# 8085_try2.net
KiCad netlist of a schematic drawn in EAGLE
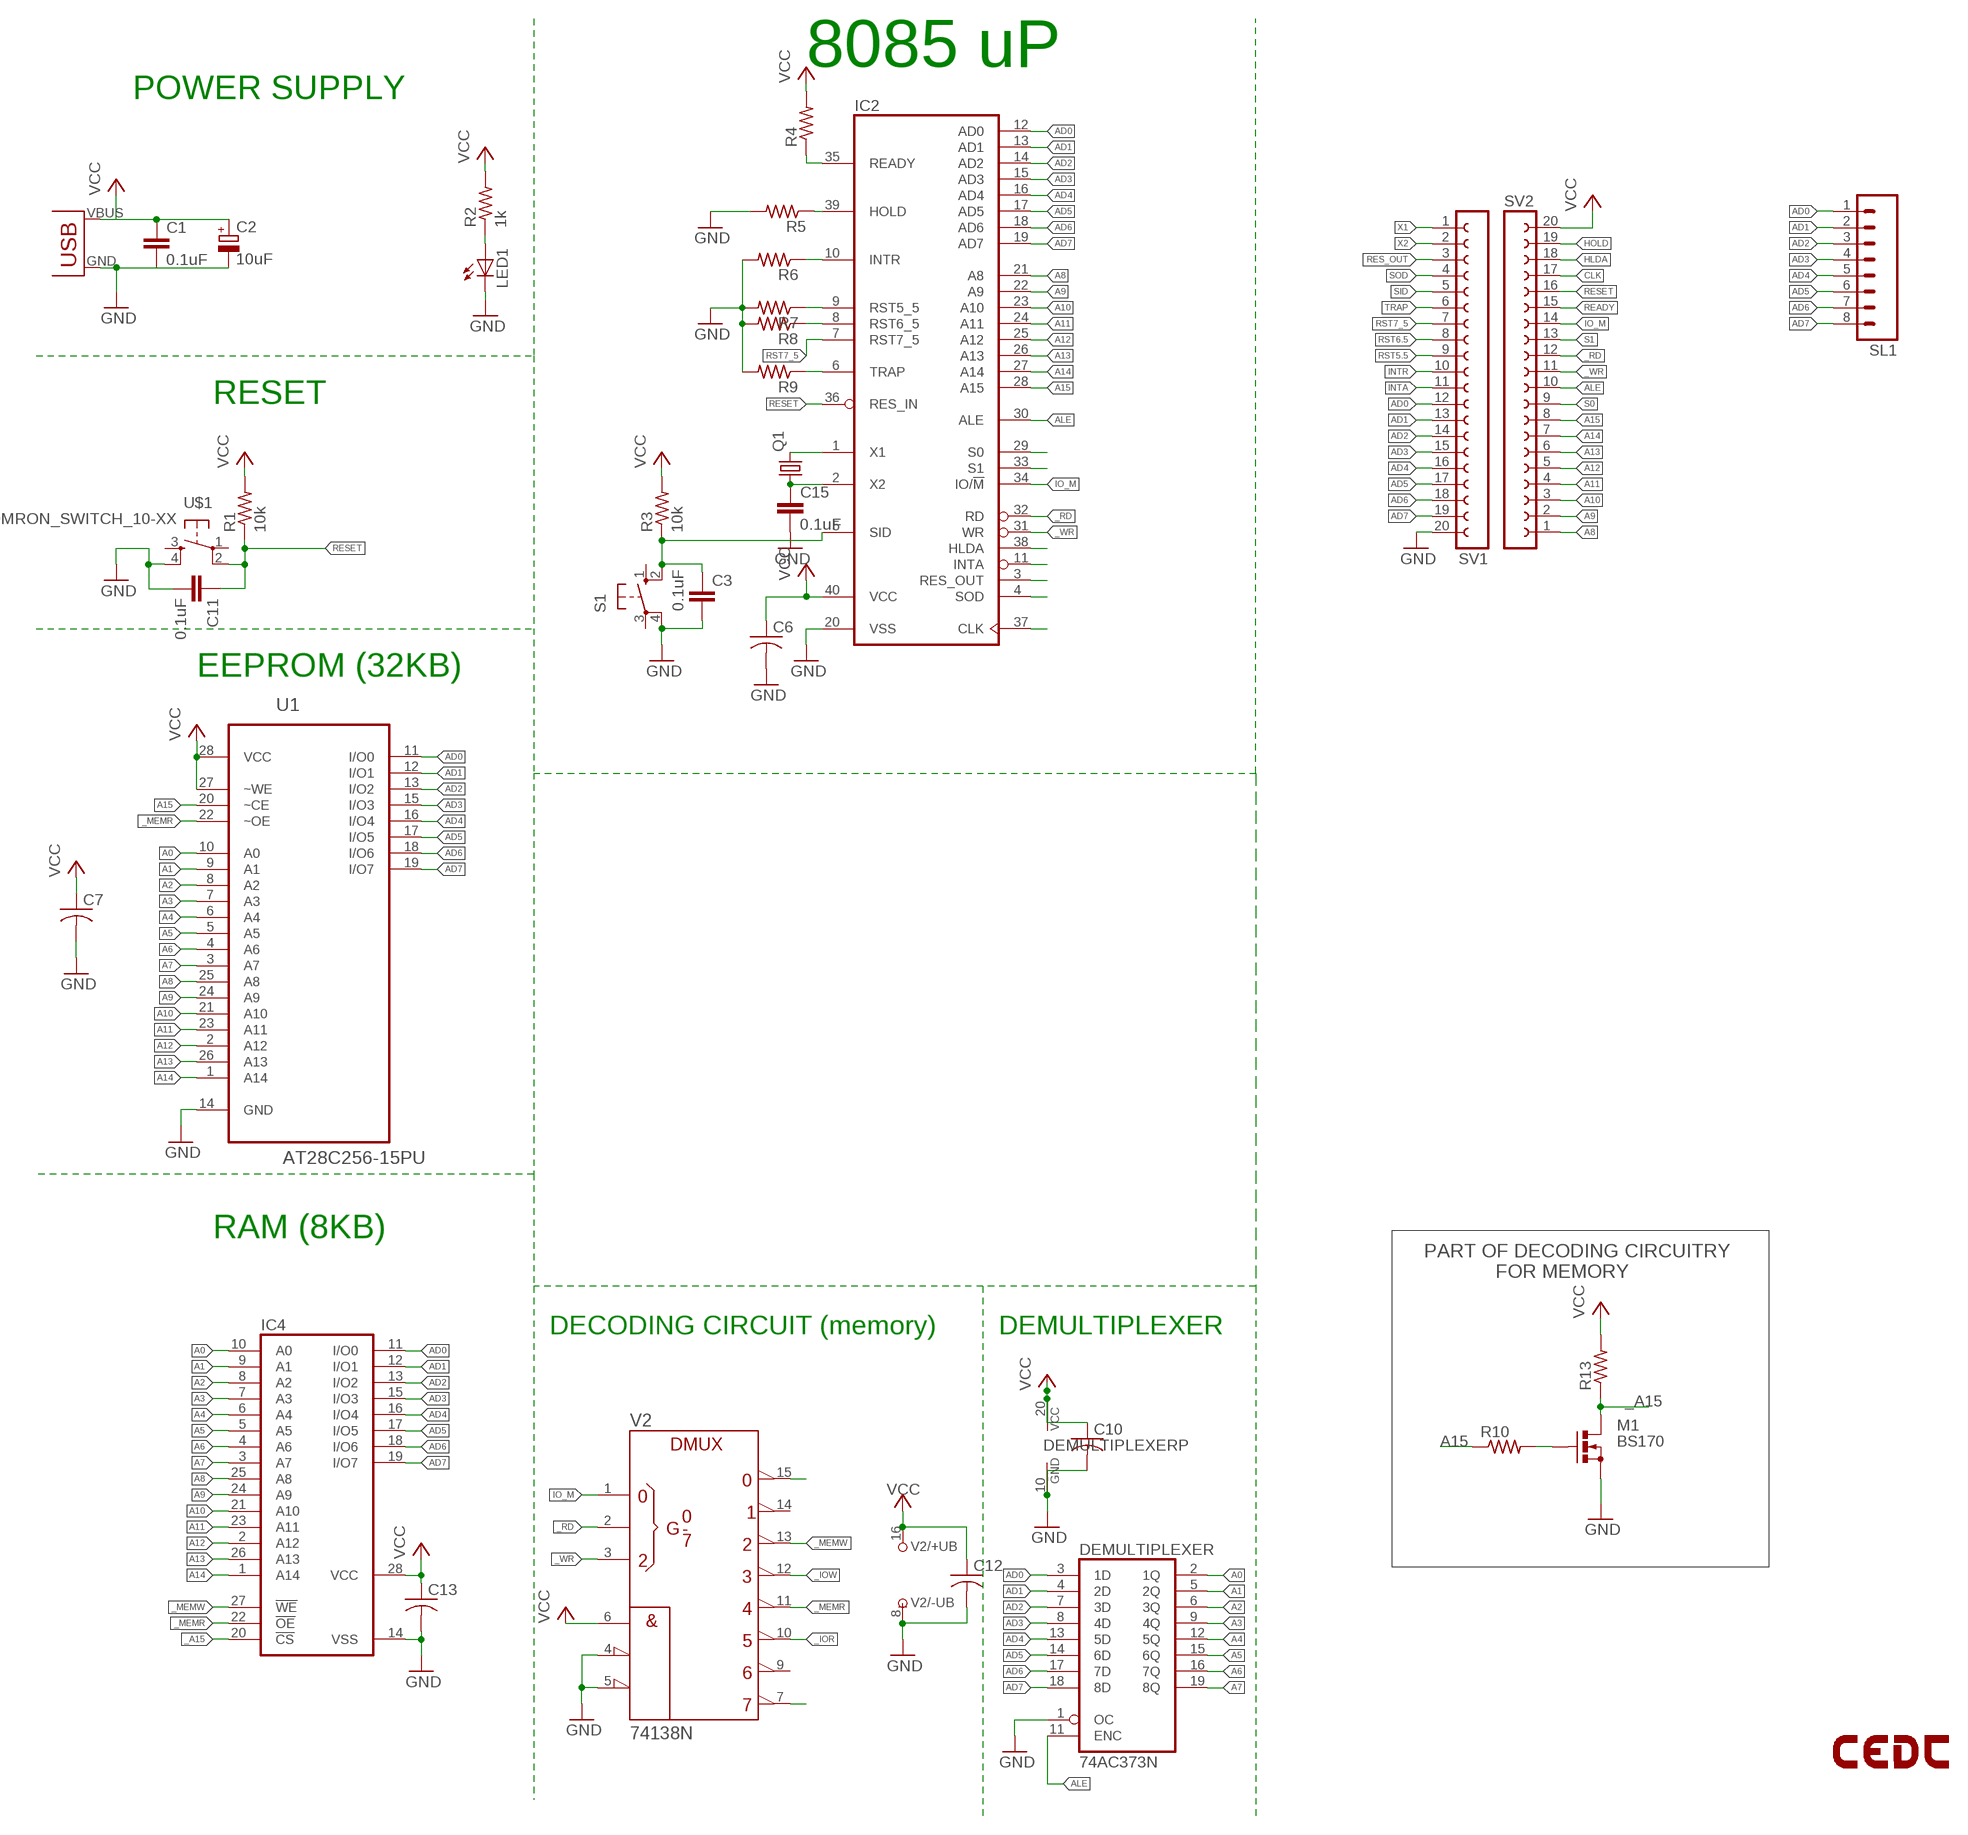
[diagram p0: schematic, sheet 1]

(export (version "E")
  (design (tool "Eeschema 10.0.6"))
  (components
    (comp (ref "C1")
      (value "0.1uF")
      (footprint "eagle-import:C2.5-3")
      (libsource (lib "eagle-import") (part "C2,5-3"))
    )
    (comp (ref "C2")
      (value "10uF")
      (footprint "eagle-import:E2,5-6")
      (libsource (lib "eagle-import") (part "CPOL-EUE2.5-6"))
    )
    (comp (ref "C3")
      (value "0.1uF")
      (footprint "eagle-import:C2.5-3")
      (libsource (lib "eagle-import") (part "C2,5-3"))
    )
    (comp (ref "C6")
      (value "CAP0805")
      (footprint "eagle-import:C0805")
      (libsource (lib "eagle-import") (part "CAP0805"))
    )
    (comp (ref "C7")
      (value "CAP0805")
      (footprint "eagle-import:C0805")
      (libsource (lib "eagle-import") (part "CAP0805"))
    )
    (comp (ref "C10")
      (value "CAP0805")
      (footprint "eagle-import:C0805")
      (libsource (lib "eagle-import") (part "CAP0805"))
    )
    (comp (ref "C11")
      (value "0.1uF")
      (footprint "eagle-import:C2.5-3")
      (libsource (lib "eagle-import") (part "C2,5-3"))
    )
    (comp (ref "C12")
      (value "CAP0805")
      (footprint "eagle-import:C0805")
      (libsource (lib "eagle-import") (part "CAP0805"))
    )
    (comp (ref "C13")
      (value "CAP0805")
      (footprint "eagle-import:C0805")
      (libsource (lib "eagle-import") (part "CAP0805"))
    )
    (comp (ref "C15")
      (value "0.1uF")
      (footprint "eagle-import:C2.5-3")
      (libsource (lib "eagle-import") (part "C2,5-3"))
    )
    (comp (ref "DEMULTIPLEXER")
      (value "74AC373N")
      (footprint "eagle-import:DIL20")
      (libsource (lib "eagle-import") (part "74373NAC"))
    )
    (comp (ref "IC2")
      (value "8085")
      (footprint "eagle-import:DIL40")
      (libsource (lib "eagle-import") (part "8085"))
    )
    (comp (ref "IC4")
      (value "62256P")
      (footprint "eagle-import:DIL28-6")
      (libsource (lib "eagle-import") (part "62256P"))
    )
    (comp (ref "LED1")
      (value "LED3MM")
      (footprint "eagle-import:LED3MM")
      (libsource (lib "eagle-import") (part "LED3MM"))
    )
    (comp (ref "LOGO1")
      (value "LOGO-CEDTBOT-18MM")
      (footprint "eagle-import:LOGO-CEDT-BOT-18MM")
      (libsource (lib "eagle-import") (part "LOGO-CEDTBOT-18MM"))
    )
    (comp (ref "M1")
      (value "BS170")
      (footprint "eagle-import:SOT54E")
      (libsource (lib "eagle-import") (part "BS170"))
    )
    (comp (ref "Q1")
      (value "CRYSTALHC49US")
      (footprint "eagle-import:HC49US")
      (libsource (lib "eagle-import") (part "CRYSTALHC49US"))
    )
    (comp (ref "R1")
      (value "10k")
      (footprint "eagle-import:0207_7")
      (libsource (lib "eagle-import") (part "RESISTOR0207/7"))
    )
    (comp (ref "R2")
      (value "1k")
      (footprint "eagle-import:0207_7")
      (libsource (lib "eagle-import") (part "RESISTOR0207/7"))
    )
    (comp (ref "R3")
      (value "10k")
      (footprint "eagle-import:0207_7")
      (libsource (lib "eagle-import") (part "RESISTOR0207/7"))
    )
    (comp (ref "R4")
      (value "RESISTOR0805")
      (footprint "eagle-import:R0805")
      (libsource (lib "eagle-import") (part "RESISTOR0805"))
    )
    (comp (ref "R5")
      (value "RESISTOR0805")
      (footprint "eagle-import:R0805")
      (libsource (lib "eagle-import") (part "RESISTOR0805"))
    )
    (comp (ref "R6")
      (value "RESISTOR0805")
      (footprint "eagle-import:R0805")
      (libsource (lib "eagle-import") (part "RESISTOR0805"))
    )
    (comp (ref "R7")
      (value "RESISTOR0805")
      (footprint "eagle-import:R0805")
      (libsource (lib "eagle-import") (part "RESISTOR0805"))
    )
    (comp (ref "R8")
      (value "RESISTOR0805")
      (footprint "eagle-import:R0805")
      (libsource (lib "eagle-import") (part "RESISTOR0805"))
    )
    (comp (ref "R9")
      (value "RESISTOR0805")
      (footprint "eagle-import:R0805")
      (libsource (lib "eagle-import") (part "RESISTOR0805"))
    )
    (comp (ref "R10")
      (value "R-US_0204/5")
      (footprint "eagle-import:0204_5")
      (libsource (lib "eagle-import") (part "R-US_0204/5"))
    )
    (comp (ref "R13")
      (value "R-US_0204/5")
      (footprint "eagle-import:0204_5")
      (libsource (lib "eagle-import") (part "R-US_0204/5"))
    )
    (comp (ref "S1")
      (value "40-XX")
      (footprint "eagle-import:B3F-40XX")
      (fields (field (name "MF") "OMRON COMPONENTS USA") (field (name "MPN") "B3F-4000"))
      (libsource (lib "eagle-import") (part "40-XX"))
    )
    (comp (ref "SL1")
      (value "M08")
      (footprint "eagle-import:08P")
      (libsource (lib "eagle-import") (part "M08"))
    )
    (comp (ref "SV1")
      (value "FE20-1")
      (footprint "eagle-import:FE20")
      (libsource (lib "eagle-import") (part "FE20-1"))
    )
    (comp (ref "SV2")
      (value "FE20-1")
      (footprint "eagle-import:FE20")
      (libsource (lib "eagle-import") (part "FE20-1"))
    )
    (comp (ref "U$1")
      (value "OMRON_SWITCH_10-XX")
      (footprint "eagle-import:B3F-10XX")
      (libsource (lib "eagle-import") (part "OMRON_SWITCH_10-XX"))
    )
    (comp (ref "U$2")
      (value "USB(POWER)")
      (footprint "eagle-import:USB(POWER)")
      (libsource (lib "eagle-import") (part "USB(POWER)"))
    )
    (comp (ref "U1")
      (value "AT28C256-15PU")
      (footprint "eagle-import:DIP254P1524X482-28")
      (fields (field (name "MF") "Microchip"))
      (libsource (lib "eagle-import") (part "AT28C256-15PU"))
    )
    (comp (ref "V2")
      (value "74138N")
      (footprint "eagle-import:DIL16")
      (libsource (lib "eagle-import") (part "74138N"))
    )
  )
  (nets
    (net (code "1") (name "A0") (class "Default")
      (node (ref "DEMULTIPLEXER") (pin "2") (pinfunction "1Q_2") (pintype "tri_state"))
      (node (ref "IC4") (pin "10") (pinfunction "A0_10") (pintype "input"))
      (node (ref "U1") (pin "10") (pinfunction "A0_10") (pintype "input"))
    )
    (net (code "2") (name "A1") (class "Default")
      (node (ref "DEMULTIPLEXER") (pin "5") (pinfunction "2Q_5") (pintype "tri_state"))
      (node (ref "IC4") (pin "9") (pinfunction "A1_9") (pintype "input"))
      (node (ref "U1") (pin "9") (pinfunction "A1_9") (pintype "input"))
    )
    (net (code "3") (name "A2") (class "Default")
      (node (ref "DEMULTIPLEXER") (pin "6") (pinfunction "3Q_6") (pintype "tri_state"))
      (node (ref "IC4") (pin "8") (pinfunction "A2_8") (pintype "input"))
      (node (ref "U1") (pin "8") (pinfunction "A2_8") (pintype "input"))
    )
    (net (code "4") (name "A3") (class "Default")
      (node (ref "DEMULTIPLEXER") (pin "9") (pinfunction "4Q_9") (pintype "tri_state"))
      (node (ref "IC4") (pin "7") (pinfunction "A3_7") (pintype "input"))
      (node (ref "U1") (pin "7") (pinfunction "A3_7") (pintype "input"))
    )
    (net (code "5") (name "A4") (class "Default")
      (node (ref "DEMULTIPLEXER") (pin "12") (pinfunction "5Q_12") (pintype "tri_state"))
      (node (ref "IC4") (pin "6") (pinfunction "A4_6") (pintype "input"))
      (node (ref "U1") (pin "6") (pinfunction "A4_6") (pintype "input"))
    )
    (net (code "6") (name "A5") (class "Default")
      (node (ref "DEMULTIPLEXER") (pin "15") (pinfunction "6Q_15") (pintype "tri_state"))
      (node (ref "IC4") (pin "5") (pinfunction "A5_5") (pintype "input"))
      (node (ref "U1") (pin "5") (pinfunction "A5_5") (pintype "input"))
    )
    (net (code "7") (name "A6") (class "Default")
      (node (ref "DEMULTIPLEXER") (pin "16") (pinfunction "7Q_16") (pintype "tri_state"))
      (node (ref "IC4") (pin "4") (pinfunction "A6_4") (pintype "input"))
      (node (ref "U1") (pin "4") (pinfunction "A6_4") (pintype "input"))
    )
    (net (code "8") (name "A7") (class "Default")
      (node (ref "DEMULTIPLEXER") (pin "19") (pinfunction "8Q_19") (pintype "tri_state"))
      (node (ref "IC4") (pin "3") (pinfunction "A7_3") (pintype "input"))
      (node (ref "U1") (pin "3") (pinfunction "A7_3") (pintype "input"))
    )
    (net (code "9") (name "A8") (class "Default")
      (node (ref "IC2") (pin "21") (pinfunction "A8_21") (pintype "output"))
      (node (ref "IC4") (pin "25") (pinfunction "A8_25") (pintype "input"))
      (node (ref "SV2") (pin "1") (pinfunction "1_1") (pintype "passive"))
      (node (ref "U1") (pin "25") (pinfunction "A8_25") (pintype "input"))
    )
    (net (code "10") (name "A9") (class "Default")
      (node (ref "IC2") (pin "22") (pinfunction "A9_22") (pintype "output"))
      (node (ref "IC4") (pin "24") (pinfunction "A9_24") (pintype "input"))
      (node (ref "SV2") (pin "2") (pinfunction "2_2") (pintype "passive"))
      (node (ref "U1") (pin "24") (pinfunction "A9_24") (pintype "input"))
    )
    (net (code "11") (name "A10") (class "Default")
      (node (ref "IC2") (pin "23") (pinfunction "A10_23") (pintype "output"))
      (node (ref "IC4") (pin "21") (pinfunction "A10_21") (pintype "input"))
      (node (ref "SV2") (pin "3") (pinfunction "3_3") (pintype "passive"))
      (node (ref "U1") (pin "21") (pinfunction "A10_21") (pintype "input"))
    )
    (net (code "12") (name "A11") (class "Default")
      (node (ref "IC2") (pin "24") (pinfunction "A11_24") (pintype "output"))
      (node (ref "IC4") (pin "23") (pinfunction "A11_23") (pintype "input"))
      (node (ref "SV2") (pin "4") (pinfunction "4_4") (pintype "passive"))
      (node (ref "U1") (pin "23") (pinfunction "A11_23") (pintype "input"))
    )
    (net (code "13") (name "A12") (class "Default")
      (node (ref "IC2") (pin "25") (pinfunction "A12_25") (pintype "output"))
      (node (ref "IC4") (pin "2") (pinfunction "A12_2") (pintype "input"))
      (node (ref "SV2") (pin "5") (pinfunction "5_5") (pintype "passive"))
      (node (ref "U1") (pin "2") (pinfunction "A12_2") (pintype "input"))
    )
    (net (code "14") (name "A13") (class "Default")
      (node (ref "IC2") (pin "26") (pinfunction "A13_26") (pintype "output"))
      (node (ref "IC4") (pin "26") (pinfunction "A13_26") (pintype "input"))
      (node (ref "SV2") (pin "6") (pinfunction "6_6") (pintype "passive"))
      (node (ref "U1") (pin "26") (pinfunction "A13_26") (pintype "input"))
    )
    (net (code "15") (name "A14") (class "Default")
      (node (ref "IC2") (pin "27") (pinfunction "A14_27") (pintype "output"))
      (node (ref "IC4") (pin "1") (pinfunction "A14_1") (pintype "input"))
      (node (ref "SV2") (pin "7") (pinfunction "7_7") (pintype "passive"))
      (node (ref "U1") (pin "1") (pinfunction "A14_1") (pintype "input"))
    )
    (net (code "16") (name "A15") (class "Default")
      (node (ref "IC2") (pin "28") (pinfunction "A15_28") (pintype "output"))
      (node (ref "R10") (pin "1") (pinfunction "1_1") (pintype "passive"))
      (node (ref "SV2") (pin "8") (pinfunction "8_8") (pintype "passive"))
      (node (ref "U1") (pin "20") (pinfunction "~{CE}_20") (pintype "input"))
    )
    (net (code "17") (name "AD0") (class "Default")
      (node (ref "DEMULTIPLEXER") (pin "3") (pinfunction "1D_3") (pintype "input"))
      (node (ref "IC2") (pin "12") (pinfunction "AD0_12") (pintype "bidirectional"))
      (node (ref "IC4") (pin "11") (pinfunction "I/O0_11") (pintype "bidirectional"))
      (node (ref "SL1") (pin "1") (pinfunction "1_1") (pintype "passive"))
      (node (ref "SV1") (pin "12") (pinfunction "12_12") (pintype "passive"))
      (node (ref "U1") (pin "11") (pinfunction "I/O0_11") (pintype "bidirectional"))
    )
    (net (code "18") (name "AD1") (class "Default")
      (node (ref "DEMULTIPLEXER") (pin "4") (pinfunction "2D_4") (pintype "input"))
      (node (ref "IC2") (pin "13") (pinfunction "AD1_13") (pintype "bidirectional"))
      (node (ref "IC4") (pin "12") (pinfunction "I/O1_12") (pintype "bidirectional"))
      (node (ref "SL1") (pin "2") (pinfunction "2_2") (pintype "passive"))
      (node (ref "SV1") (pin "13") (pinfunction "13_13") (pintype "passive"))
      (node (ref "U1") (pin "12") (pinfunction "I/O1_12") (pintype "bidirectional"))
    )
    (net (code "19") (name "AD2") (class "Default")
      (node (ref "DEMULTIPLEXER") (pin "7") (pinfunction "3D_7") (pintype "input"))
      (node (ref "IC2") (pin "14") (pinfunction "AD2_14") (pintype "bidirectional"))
      (node (ref "IC4") (pin "13") (pinfunction "I/O2_13") (pintype "bidirectional"))
      (node (ref "SL1") (pin "3") (pinfunction "3_3") (pintype "passive"))
      (node (ref "SV1") (pin "14") (pinfunction "14_14") (pintype "passive"))
      (node (ref "U1") (pin "13") (pinfunction "I/O2_13") (pintype "bidirectional"))
    )
    (net (code "20") (name "AD3") (class "Default")
      (node (ref "DEMULTIPLEXER") (pin "8") (pinfunction "4D_8") (pintype "input"))
      (node (ref "IC2") (pin "15") (pinfunction "AD3_15") (pintype "bidirectional"))
      (node (ref "IC4") (pin "15") (pinfunction "I/O3_15") (pintype "bidirectional"))
      (node (ref "SL1") (pin "4") (pinfunction "4_4") (pintype "passive"))
      (node (ref "SV1") (pin "15") (pinfunction "15_15") (pintype "passive"))
      (node (ref "U1") (pin "15") (pinfunction "I/O3_15") (pintype "bidirectional"))
    )
    (net (code "21") (name "AD4") (class "Default")
      (node (ref "DEMULTIPLEXER") (pin "13") (pinfunction "5D_13") (pintype "input"))
      (node (ref "IC2") (pin "16") (pinfunction "AD4_16") (pintype "bidirectional"))
      (node (ref "IC4") (pin "16") (pinfunction "I/O4_16") (pintype "bidirectional"))
      (node (ref "SL1") (pin "5") (pinfunction "5_5") (pintype "passive"))
      (node (ref "SV1") (pin "16") (pinfunction "16_16") (pintype "passive"))
      (node (ref "U1") (pin "16") (pinfunction "I/O4_16") (pintype "bidirectional"))
    )
    (net (code "22") (name "AD5") (class "Default")
      (node (ref "DEMULTIPLEXER") (pin "14") (pinfunction "6D_14") (pintype "input"))
      (node (ref "IC2") (pin "17") (pinfunction "AD5_17") (pintype "bidirectional"))
      (node (ref "IC4") (pin "17") (pinfunction "I/O5_17") (pintype "bidirectional"))
      (node (ref "SL1") (pin "6") (pinfunction "6_6") (pintype "passive"))
      (node (ref "SV1") (pin "17") (pinfunction "17_17") (pintype "passive"))
      (node (ref "U1") (pin "17") (pinfunction "I/O5_17") (pintype "bidirectional"))
    )
    (net (code "23") (name "AD6") (class "Default")
      (node (ref "DEMULTIPLEXER") (pin "17") (pinfunction "7D_17") (pintype "input"))
      (node (ref "IC2") (pin "18") (pinfunction "AD6_18") (pintype "bidirectional"))
      (node (ref "IC4") (pin "18") (pinfunction "I/O6_18") (pintype "bidirectional"))
      (node (ref "SL1") (pin "7") (pinfunction "7_7") (pintype "passive"))
      (node (ref "SV1") (pin "18") (pinfunction "18_18") (pintype "passive"))
      (node (ref "U1") (pin "18") (pinfunction "I/O6_18") (pintype "bidirectional"))
    )
    (net (code "24") (name "AD7") (class "Default")
      (node (ref "DEMULTIPLEXER") (pin "18") (pinfunction "8D_18") (pintype "input"))
      (node (ref "IC2") (pin "19") (pinfunction "AD7_19") (pintype "bidirectional"))
      (node (ref "IC4") (pin "19") (pinfunction "I/O7_19") (pintype "bidirectional"))
      (node (ref "SL1") (pin "8") (pinfunction "8_8") (pintype "passive"))
      (node (ref "SV1") (pin "19") (pinfunction "19_19") (pintype "passive"))
      (node (ref "U1") (pin "19") (pinfunction "I/O7_19") (pintype "bidirectional"))
    )
    (net (code "25") (name "ALE") (class "Default")
      (node (ref "DEMULTIPLEXER") (pin "11") (pinfunction "ENC_11") (pintype "input"))
      (node (ref "IC2") (pin "30") (pinfunction "ALE_30") (pintype "output"))
      (node (ref "SV2") (pin "10") (pinfunction "10_10") (pintype "passive"))
    )
    (net (code "26") (name "CLK") (class "Default")
      (node (ref "IC2") (pin "37") (pinfunction "CLK_37") (pintype "output"))
      (node (ref "SV2") (pin "17") (pinfunction "17_17") (pintype "passive"))
    )
    (net (code "27") (name "GND") (class "Default")
      (node (ref "C1") (pin "2") (pinfunction "2_2") (pintype "passive"))
      (node (ref "C10") (pin "2") (pinfunction "2_2") (pintype "passive"))
      (node (ref "C11") (pin "2") (pinfunction "2_2") (pintype "passive"))
      (node (ref "C12") (pin "2") (pinfunction "2_2") (pintype "passive"))
      (node (ref "C13") (pin "2") (pinfunction "2_2") (pintype "passive"))
      (node (ref "C15") (pin "2") (pinfunction "2_2") (pintype "passive"))
      (node (ref "C2") (pin "-") (pinfunction "-_-") (pintype "passive"))
      (node (ref "C3") (pin "2") (pinfunction "2_2") (pintype "passive"))
      (node (ref "C6") (pin "2") (pinfunction "2_2") (pintype "passive"))
      (node (ref "C7") (pin "2") (pinfunction "2_2") (pintype "passive"))
      (node (ref "DEMULTIPLEXER") (pin "1") (pinfunction "OC_1") (pintype "input"))
      (node (ref "DEMULTIPLEXER") (pin "10") (pinfunction "GND_10") (pintype "power_in"))
      (node (ref "IC2") (pin "20") (pinfunction "VSS_20") (pintype "power_in"))
      (node (ref "IC4") (pin "14") (pinfunction "VSS_14") (pintype "power_in"))
      (node (ref "LED1") (pin "K") (pinfunction "C_K") (pintype "passive"))
      (node (ref "M1") (pin "S") (pinfunction "S_S") (pintype "passive"))
      (node (ref "R5") (pin "2") (pinfunction "2_2") (pintype "passive"))
      (node (ref "R6") (pin "2") (pinfunction "2_2") (pintype "passive"))
      (node (ref "R7") (pin "2") (pinfunction "2_2") (pintype "passive"))
      (node (ref "R8") (pin "2") (pinfunction "2_2") (pintype "passive"))
      (node (ref "R9") (pin "2") (pinfunction "2_2") (pintype "passive"))
      (node (ref "S1") (pin "4") (pinfunction "P1_4") (pintype "passive"))
      (node (ref "SV1") (pin "20") (pinfunction "20_20") (pintype "passive"))
      (node (ref "U$1") (pin "4") (pinfunction "S1_4") (pintype "passive"))
      (node (ref "U$2") (pin "GND") (pinfunction "GND_GND") (pintype "power_in"))
      (node (ref "U1") (pin "14") (pinfunction "GND_14") (pintype "passive"))
      (node (ref "V2") (pin "4") (pinfunction "~{G2A}_4") (pintype "input"))
      (node (ref "V2") (pin "5") (pinfunction "~{G2B}_5") (pintype "input"))
      (node (ref "V2") (pin "8") (pinfunction "-UB_8") (pintype "power_in"))
    )
    (net (code "28") (name "HLDA") (class "Default")
      (node (ref "IC2") (pin "38") (pinfunction "HLDA_38") (pintype "output"))
      (node (ref "SV2") (pin "18") (pinfunction "18_18") (pintype "passive"))
    )
    (net (code "29") (name "HOLD") (class "Default")
      (node (ref "IC2") (pin "39") (pinfunction "HOLD_39") (pintype "input"))
      (node (ref "R5") (pin "1") (pinfunction "1_1") (pintype "passive"))
      (node (ref "SV2") (pin "19") (pinfunction "19_19") (pintype "passive"))
    )
    (net (code "30") (name "INTA") (class "Default")
      (node (ref "IC2") (pin "11") (pinfunction "INTA_11") (pintype "output"))
      (node (ref "SV1") (pin "11") (pinfunction "11_11") (pintype "passive"))
    )
    (net (code "31") (name "INTR") (class "Default")
      (node (ref "IC2") (pin "10") (pinfunction "INTR_10") (pintype "input"))
      (node (ref "R6") (pin "1") (pinfunction "1_1") (pintype "passive"))
      (node (ref "SV1") (pin "10") (pinfunction "10_10") (pintype "passive"))
    )
    (net (code "32") (name "IO_M") (class "Default")
      (node (ref "IC2") (pin "34") (pinfunction "IO/~{M}_34") (pintype "output"))
      (node (ref "SV2") (pin "14") (pinfunction "14_14") (pintype "passive"))
      (node (ref "V2") (pin "1") (pinfunction "A_1") (pintype "input"))
    )
    (net (code "33") (name "Net-(LED1-PadA)") (class "Default")
      (node (ref "LED1") (pin "A") (pinfunction "A_A") (pintype "passive"))
      (node (ref "R2") (pin "1") (pinfunction "1_1") (pintype "passive"))
    )
    (net (code "34") (name "Net-(M1-PadG)") (class "Default")
      (node (ref "M1") (pin "G") (pinfunction "G_G") (pintype "passive"))
      (node (ref "R10") (pin "2") (pinfunction "2_2") (pintype "passive"))
    )
    (net (code "35") (name "READY") (class "Default")
      (node (ref "IC2") (pin "35") (pinfunction "READY_35") (pintype "input"))
      (node (ref "R4") (pin "1") (pinfunction "1_1") (pintype "passive"))
      (node (ref "SV2") (pin "15") (pinfunction "15_15") (pintype "passive"))
    )
    (net (code "36") (name "RESET") (class "Default")
      (node (ref "C11") (pin "1") (pinfunction "1_1") (pintype "passive"))
      (node (ref "IC2") (pin "36") (pinfunction "RES_IN_36") (pintype "input"))
      (node (ref "R1") (pin "1") (pinfunction "1_1") (pintype "passive"))
      (node (ref "SV2") (pin "16") (pinfunction "16_16") (pintype "passive"))
      (node (ref "U$1") (pin "2") (pinfunction "P1_2") (pintype "passive"))
    )
    (net (code "37") (name "RES_OUT") (class "Default")
      (node (ref "IC2") (pin "3") (pinfunction "RES_OUT_3") (pintype "output"))
      (node (ref "SV1") (pin "3") (pinfunction "3_3") (pintype "passive"))
    )
    (net (code "38") (name "RST5.5") (class "Default")
      (node (ref "IC2") (pin "9") (pinfunction "RST5_5_9") (pintype "input"))
      (node (ref "R7") (pin "1") (pinfunction "1_1") (pintype "passive"))
      (node (ref "SV1") (pin "9") (pinfunction "9_9") (pintype "passive"))
    )
    (net (code "39") (name "RST6.5") (class "Default")
      (node (ref "IC2") (pin "8") (pinfunction "RST6_5_8") (pintype "input"))
      (node (ref "R8") (pin "1") (pinfunction "1_1") (pintype "passive"))
      (node (ref "SV1") (pin "8") (pinfunction "8_8") (pintype "passive"))
    )
    (net (code "40") (name "RST7_5") (class "Default")
      (node (ref "IC2") (pin "7") (pinfunction "RST7_5_7") (pintype "input"))
      (node (ref "SV1") (pin "7") (pinfunction "7_7") (pintype "passive"))
    )
    (net (code "41") (name "S0") (class "Default")
      (node (ref "IC2") (pin "29") (pinfunction "S0_29") (pintype "output"))
      (node (ref "SV2") (pin "9") (pinfunction "9_9") (pintype "passive"))
    )
    (net (code "42") (name "S1") (class "Default")
      (node (ref "IC2") (pin "33") (pinfunction "S1_33") (pintype "output"))
      (node (ref "SV2") (pin "13") (pinfunction "13_13") (pintype "passive"))
    )
    (net (code "43") (name "SID") (class "Default")
      (node (ref "C3") (pin "1") (pinfunction "1_1") (pintype "passive"))
      (node (ref "IC2") (pin "5") (pinfunction "SID_5") (pintype "input"))
      (node (ref "R3") (pin "1") (pinfunction "1_1") (pintype "passive"))
      (node (ref "S1") (pin "2") (pinfunction "S1_2") (pintype "passive"))
      (node (ref "SV1") (pin "5") (pinfunction "5_5") (pintype "passive"))
    )
    (net (code "44") (name "SOD") (class "Default")
      (node (ref "IC2") (pin "4") (pinfunction "SOD_4") (pintype "output"))
      (node (ref "SV1") (pin "4") (pinfunction "4_4") (pintype "passive"))
    )
    (net (code "45") (name "TRAP") (class "Default")
      (node (ref "IC2") (pin "6") (pinfunction "TRAP_6") (pintype "input"))
      (node (ref "R9") (pin "1") (pinfunction "1_1") (pintype "passive"))
      (node (ref "SV1") (pin "6") (pinfunction "6_6") (pintype "passive"))
    )
    (net (code "46") (name "VCC") (class "Default")
      (node (ref "C1") (pin "1") (pinfunction "1_1") (pintype "passive"))
      (node (ref "C10") (pin "1") (pinfunction "1_1") (pintype "passive"))
      (node (ref "C12") (pin "1") (pinfunction "1_1") (pintype "passive"))
      (node (ref "C13") (pin "1") (pinfunction "1_1") (pintype "passive"))
      (node (ref "C2") (pin "+") (pinfunction "+_+") (pintype "passive"))
      (node (ref "C6") (pin "1") (pinfunction "1_1") (pintype "passive"))
      (node (ref "C7") (pin "1") (pinfunction "1_1") (pintype "passive"))
      (node (ref "DEMULTIPLEXER") (pin "20") (pinfunction "VCC_20") (pintype "power_in"))
      (node (ref "IC2") (pin "40") (pinfunction "VCC_40") (pintype "power_in"))
      (node (ref "IC4") (pin "28") (pinfunction "VCC_28") (pintype "power_in"))
      (node (ref "R1") (pin "2") (pinfunction "2_2") (pintype "passive"))
      (node (ref "R13") (pin "2") (pinfunction "2_2") (pintype "passive"))
      (node (ref "R2") (pin "2") (pinfunction "2_2") (pintype "passive"))
      (node (ref "R3") (pin "2") (pinfunction "2_2") (pintype "passive"))
      (node (ref "R4") (pin "2") (pinfunction "2_2") (pintype "passive"))
      (node (ref "SV2") (pin "20") (pinfunction "20_20") (pintype "passive"))
      (node (ref "U$2") (pin "VBUS") (pinfunction "VCC_VBUS") (pintype "power_in"))
      (node (ref "U1") (pin "27") (pinfunction "~{WE}_27") (pintype "input"))
      (node (ref "U1") (pin "28") (pinfunction "VCC_28") (pintype "power_in"))
      (node (ref "V2") (pin "16") (pinfunction "+UB_16") (pintype "power_in"))
      (node (ref "V2") (pin "6") (pinfunction "G1_6") (pintype "input"))
    )
    (net (code "47") (name "X1") (class "Default")
      (node (ref "IC2") (pin "1") (pinfunction "X1_1") (pintype "input"))
      (node (ref "Q1") (pin "2") (pinfunction "2_2") (pintype "passive"))
      (node (ref "SV1") (pin "1") (pinfunction "1_1") (pintype "passive"))
    )
    (net (code "48") (name "X2") (class "Default")
      (node (ref "C15") (pin "1") (pinfunction "1_1") (pintype "passive"))
      (node (ref "IC2") (pin "2") (pinfunction "X2_2") (pintype "input"))
      (node (ref "Q1") (pin "1") (pinfunction "1_1") (pintype "passive"))
      (node (ref "SV1") (pin "2") (pinfunction "2_2") (pintype "passive"))
    )
    (net (code "49") (name "_A15") (class "Default")
      (node (ref "IC4") (pin "20") (pinfunction "~{CS}_20") (pintype "input"))
      (node (ref "M1") (pin "D") (pinfunction "D_D") (pintype "passive"))
      (node (ref "R13") (pin "1") (pinfunction "1_1") (pintype "passive"))
    )
    (net (code "50") (name "_IOR") (class "Default")
      (node (ref "V2") (pin "10") (pinfunction "Y5_10") (pintype "output"))
    )
    (net (code "51") (name "_IOW") (class "Default")
      (node (ref "V2") (pin "12") (pinfunction "Y3_12") (pintype "output"))
    )
    (net (code "52") (name "_MEMR") (class "Default")
      (node (ref "IC4") (pin "22") (pinfunction "~{OE}_22") (pintype "input"))
      (node (ref "U1") (pin "22") (pinfunction "~{OE}_22") (pintype "input"))
      (node (ref "V2") (pin "11") (pinfunction "Y4_11") (pintype "output"))
    )
    (net (code "53") (name "_MEMW") (class "Default")
      (node (ref "IC4") (pin "27") (pinfunction "~{WE}_27") (pintype "input"))
      (node (ref "V2") (pin "13") (pinfunction "Y2_13") (pintype "output"))
    )
    (net (code "54") (name "_RD") (class "Default")
      (node (ref "IC2") (pin "32") (pinfunction "RD_32") (pintype "output"))
      (node (ref "SV2") (pin "12") (pinfunction "12_12") (pintype "passive"))
      (node (ref "V2") (pin "2") (pinfunction "B_2") (pintype "input"))
    )
    (net (code "55") (name "_WR") (class "Default")
      (node (ref "IC2") (pin "31") (pinfunction "WR_31") (pintype "output"))
      (node (ref "SV2") (pin "11") (pinfunction "11_11") (pintype "passive"))
      (node (ref "V2") (pin "3") (pinfunction "C_3") (pintype "input"))
    )
    (net (code "56") (name "unconnected-(S1-P-Pad3)") (class "Default")
      (node (ref "S1") (pin "3") (pinfunction "P_3") (pintype "passive"))
    )
    (net (code "57") (name "unconnected-(S1-S-Pad1)") (class "Default")
      (node (ref "S1") (pin "1") (pinfunction "S_1") (pintype "passive"))
    )
    (net (code "58") (name "unconnected-(U$1-P-Pad1)") (class "Default")
      (node (ref "U$1") (pin "1") (pinfunction "P_1") (pintype "passive"))
    )
    (net (code "59") (name "unconnected-(U$1-S-Pad3)") (class "Default")
      (node (ref "U$1") (pin "3") (pinfunction "S_3") (pintype "passive"))
    )
    (net (code "60") (name "unconnected-(V2C-Y0-Pad15)") (class "Default")
      (node (ref "V2") (pin "15") (pinfunction "Y0_15") (pintype "output"))
    )
    (net (code "61") (name "unconnected-(V2C-Y1-Pad14)") (class "Default")
      (node (ref "V2") (pin "14") (pinfunction "Y1_14") (pintype "output"))
    )
    (net (code "62") (name "unconnected-(V2C-Y6-Pad9)") (class "Default")
      (node (ref "V2") (pin "9") (pinfunction "Y6_9") (pintype "output"))
    )
    (net (code "63") (name "unconnected-(V2C-Y7-Pad7)") (class "Default")
      (node (ref "V2") (pin "7") (pinfunction "Y7_7") (pintype "output"))
    )
  )
)
